# Crossover_HP.net
KiCad netlist of a schematic drawn in EAGLE
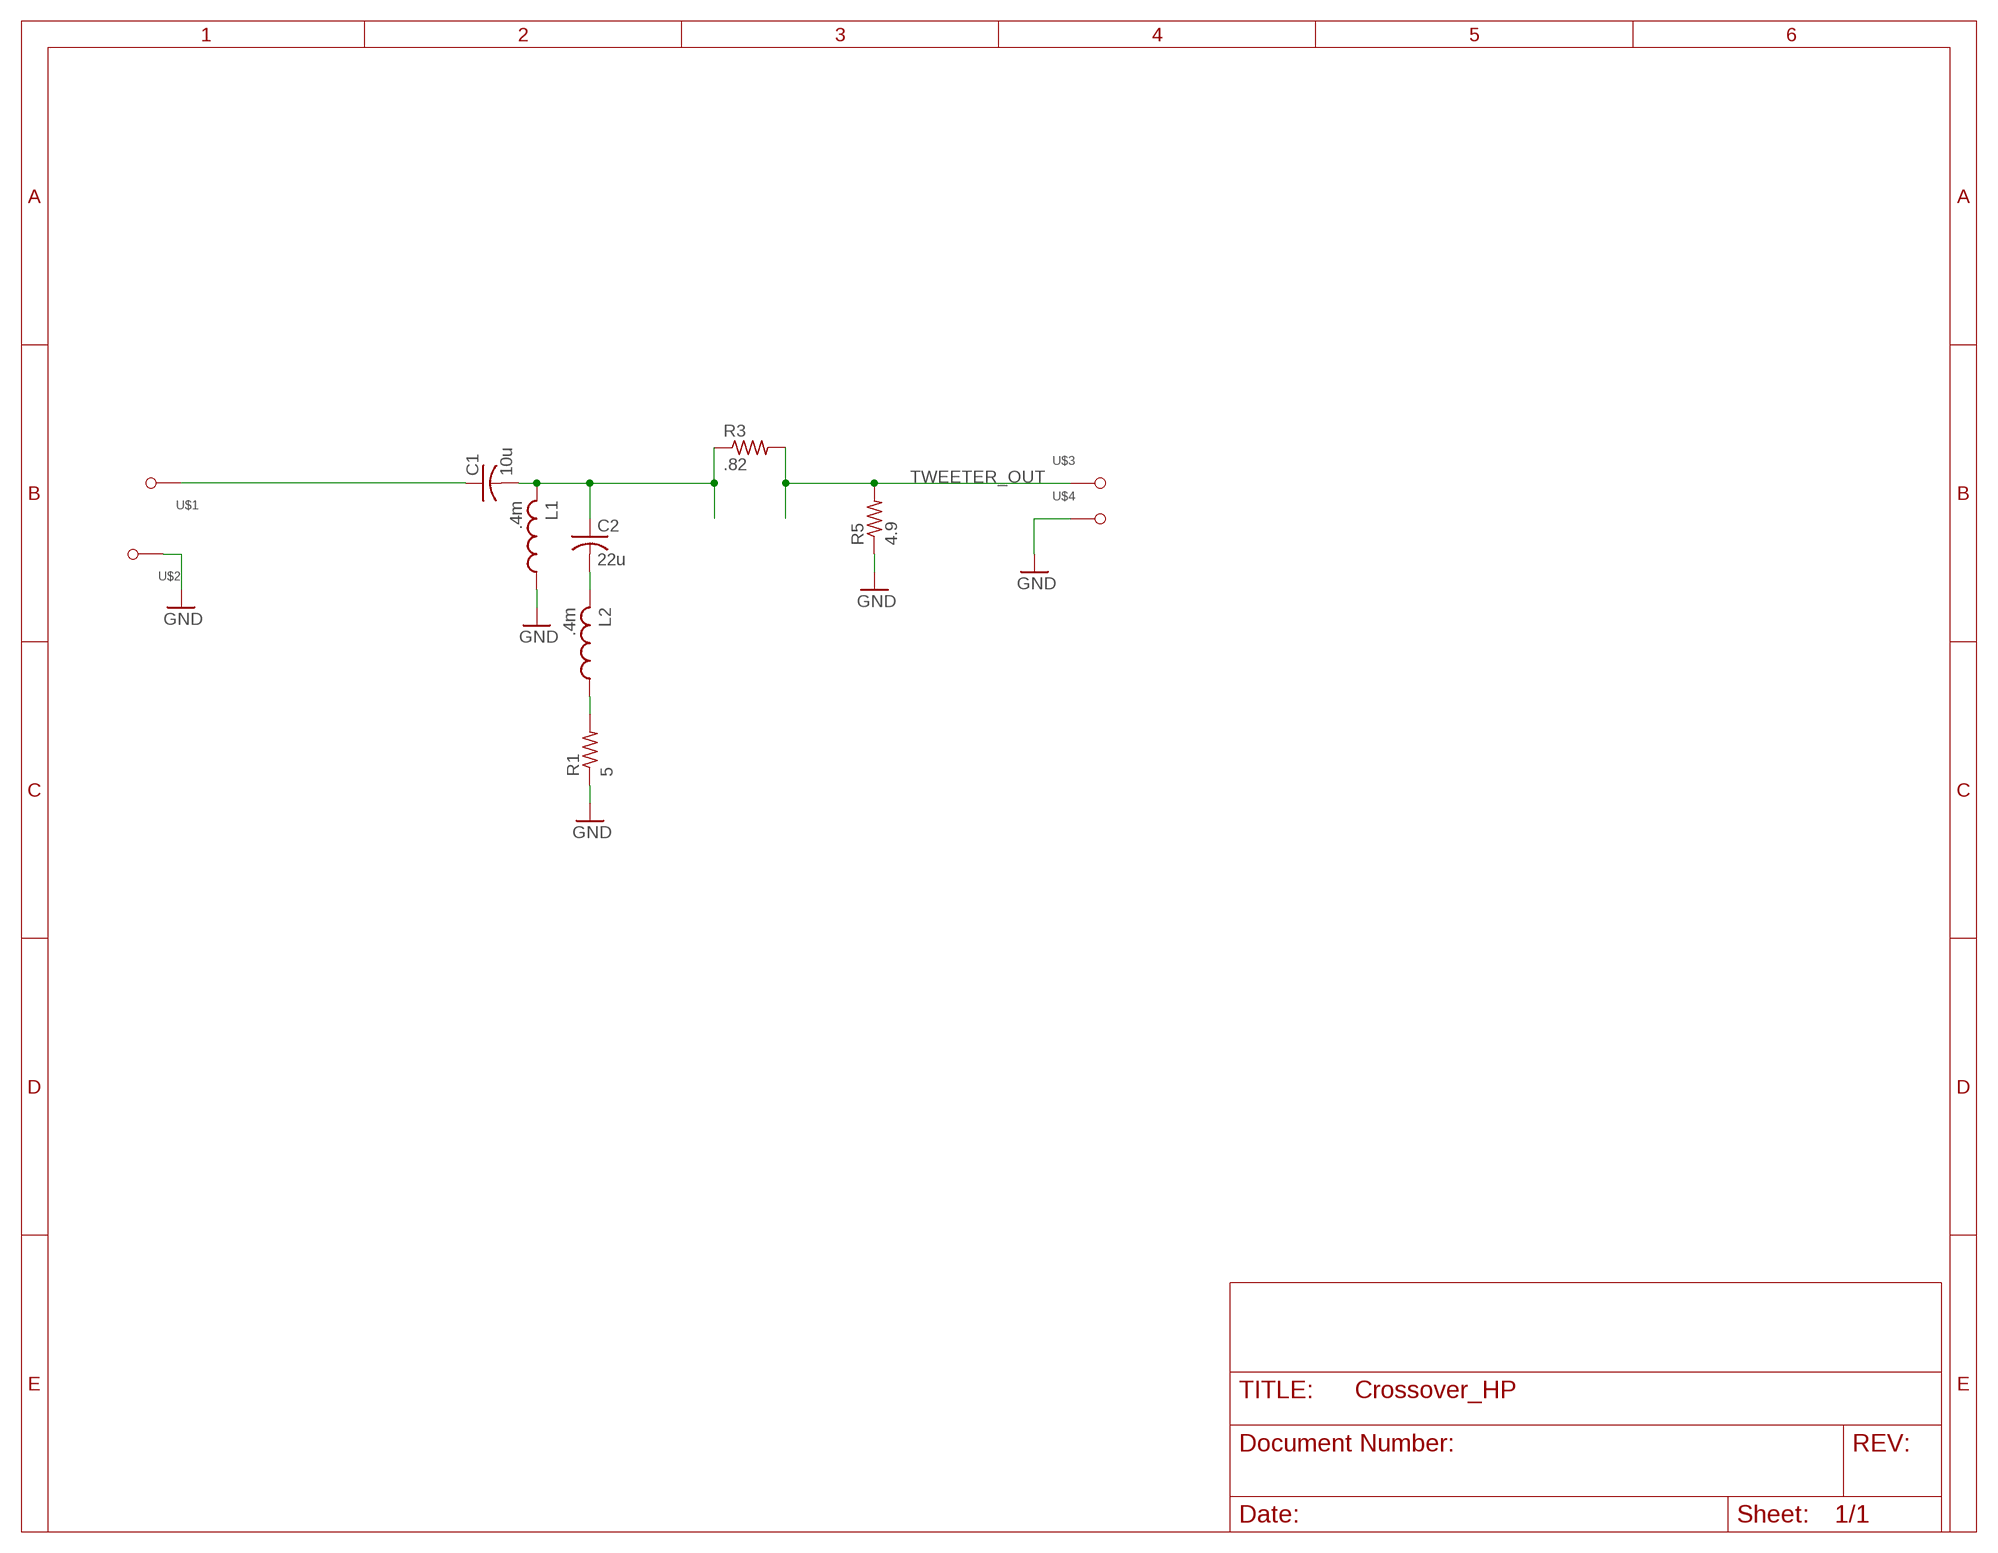
[diagram p0: schematic, sheet 1]

(export (version "E")
  (design (tool "Eeschema 10.0.6"))
  (components
    (comp (ref "C1")
      (value "10u")
      (footprint "eagle-import:3.5MMP_8MMP")
      (libsource (lib "eagle-import") (part "C-USC3.5MMP_8MMD"))
    )
    (comp (ref "C2")
      (value "22u")
      (footprint "eagle-import:5MMP_10MMD")
      (libsource (lib "eagle-import") (part "C-USC5MMP_10MMD"))
    )
    (comp (ref "L1")
      (value ".4m")
      (footprint "eagle-import:AIR_COIL_2INX3_4IN")
      (libsource (lib "eagle-import") (part "L-US"))
    )
    (comp (ref "L2")
      (value ".4m")
      (footprint "eagle-import:AIR_COIL_2INX3_4IN")
      (libsource (lib "eagle-import") (part "L-US"))
    )
    (comp (ref "R1")
      (value "5")
      (footprint "eagle-import:9.5MMX9MMX22MM")
      (libsource (lib "eagle-import") (part "R-US_5W"))
    )
    (comp (ref "R3")
      (value ".82")
      (footprint "eagle-import:9.5MMX9MMX48MM")
      (libsource (lib "eagle-import") (part "R-US_10W"))
    )
    (comp (ref "R5")
      (value "4.9")
      (footprint "eagle-import:9.5MMX9MMX48MM")
      (libsource (lib "eagle-import") (part "R-US_10W"))
    )
    (comp (ref "U$1")
      (value "18AWG_HOLE")
      (footprint "eagle-import:18AWG_HOLE")
      (libsource (lib "eagle-import") (part "18AWG_HOLE"))
    )
    (comp (ref "U$2")
      (value "18AWG_HOLE")
      (footprint "eagle-import:18AWG_HOLE")
      (libsource (lib "eagle-import") (part "18AWG_HOLE"))
    )
    (comp (ref "U$3")
      (value "18AWG_HOLE")
      (footprint "eagle-import:18AWG_HOLE")
      (libsource (lib "eagle-import") (part "18AWG_HOLE"))
    )
    (comp (ref "U$4")
      (value "18AWG_HOLE")
      (footprint "eagle-import:18AWG_HOLE")
      (libsource (lib "eagle-import") (part "18AWG_HOLE"))
    )
  )
  (nets
    (net (code "1") (name "/TWEETER_OUT") (class "Default")
      (node (ref "R3") (pin "P$2") (pinfunction "2_P$2") (pintype "passive"))
      (node (ref "R5") (pin "P$2") (pinfunction "2_P$2") (pintype "passive"))
      (node (ref "U$3") (pin "P$1") (pinfunction ">NAME_P$1") (pintype "passive"))
    )
    (net (code "2") (name "GND") (class "Default")
      (node (ref "L1") (pin "P$1") (pinfunction "1_P$1") (pintype "passive"))
      (node (ref "R1") (pin "P$1") (pinfunction "1_P$1") (pintype "passive"))
      (node (ref "R5") (pin "P$1") (pinfunction "1_P$1") (pintype "passive"))
      (node (ref "U$2") (pin "P$1") (pinfunction ">NAME_P$1") (pintype "passive"))
      (node (ref "U$4") (pin "P$1") (pinfunction ">NAME_P$1") (pintype "passive"))
    )
    (net (code "3") (name "Net-(C1-1)") (class "Default")
      (node (ref "C1") (pin "POS") (pinfunction "1_POS") (pintype "passive"))
      (node (ref "U$1") (pin "P$1") (pinfunction ">NAME_P$1") (pintype "passive"))
    )
    (net (code "4") (name "Net-(C1-2)") (class "Default")
      (node (ref "C1") (pin "NEG") (pinfunction "2_NEG") (pintype "passive"))
      (node (ref "C2") (pin "POS") (pinfunction "1_POS") (pintype "passive"))
      (node (ref "L1") (pin "P$2") (pinfunction "2_P$2") (pintype "passive"))
      (node (ref "R3") (pin "P$1") (pinfunction "1_P$1") (pintype "passive"))
    )
    (net (code "5") (name "Net-(C2-2)") (class "Default")
      (node (ref "C2") (pin "NEG") (pinfunction "2_NEG") (pintype "passive"))
      (node (ref "L2") (pin "P$2") (pinfunction "2_P$2") (pintype "passive"))
    )
    (net (code "6") (name "Net-(L2-1)") (class "Default")
      (node (ref "L2") (pin "P$1") (pinfunction "1_P$1") (pintype "passive"))
      (node (ref "R1") (pin "P$2") (pinfunction "2_P$2") (pintype "passive"))
    )
  )
)
